# Driver4.net
KiCad netlist of a schematic drawn in Altium Designer
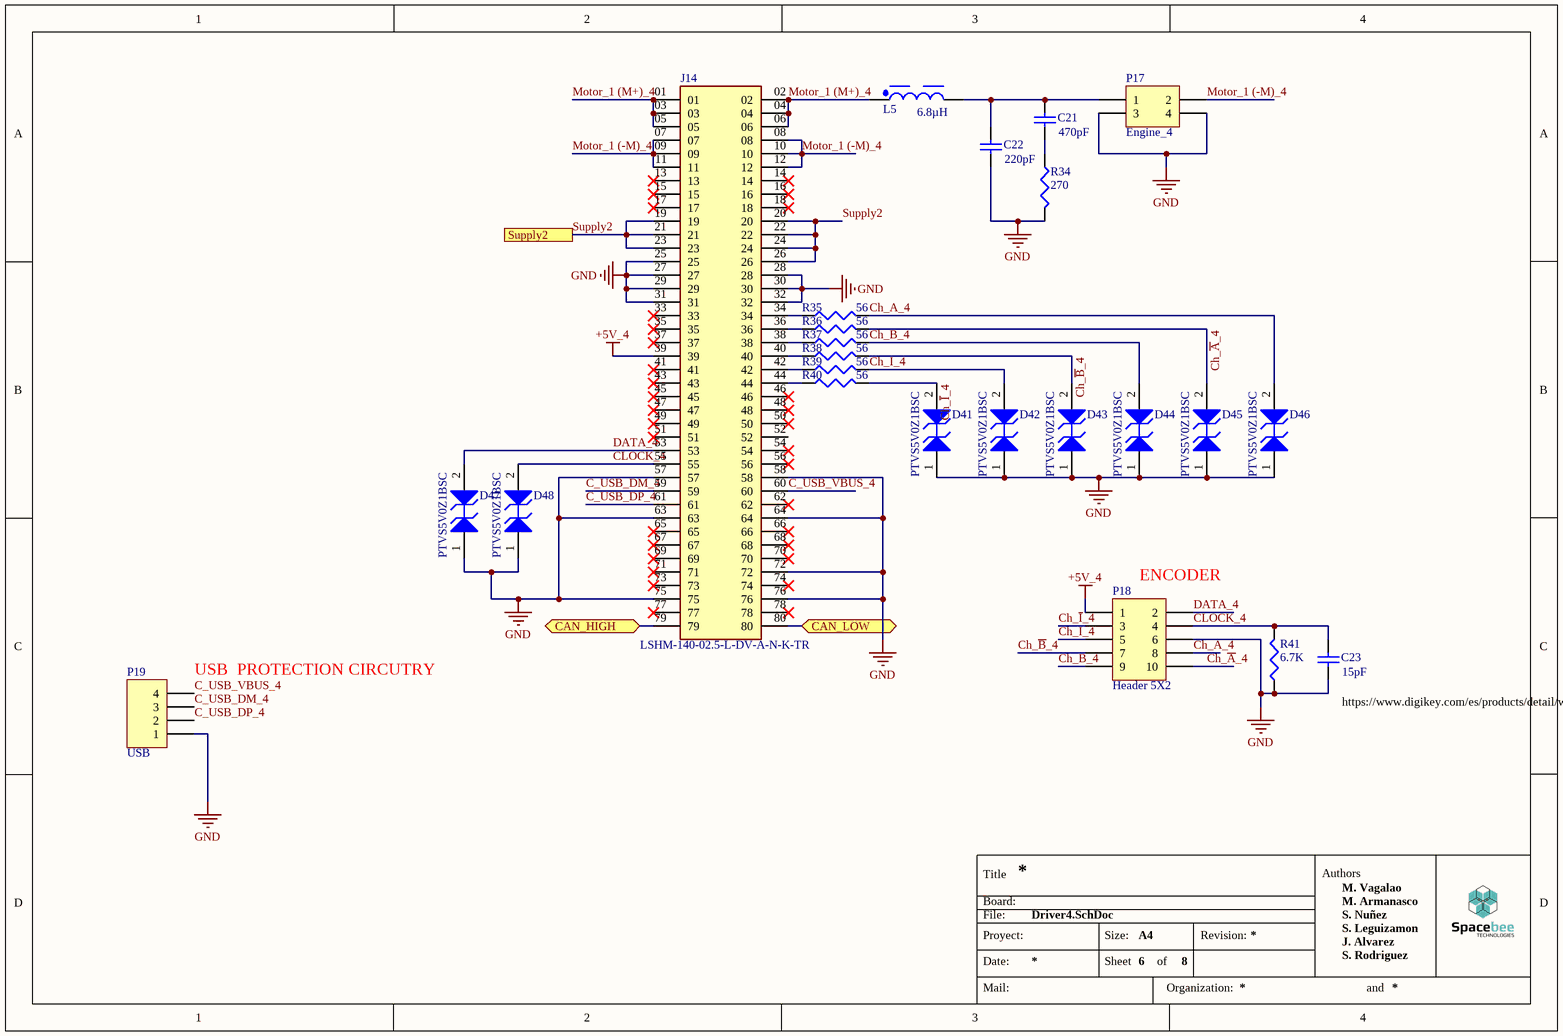
[diagram p0: Driver4.SchDoc]

(export (version "E")
  (design (tool "Eeschema 10.0.6"))
  (components
    (comp (ref "C21")
      (value "470pF")
      (footprint "1608[0603]")
      (description "Capacitor (Semiconductor SIM Model)")
      (fields (field (name "Comment") "Cap Semi") (field (name "PUBLISHER") "Altium Limited"))
      (libsource (lib "Miscellaneous Devices") (part "Cap Semi"))
    )
    (comp (ref "C22")
      (value "220pF")
      (footprint "1608[0603]")
      (description "Capacitor (Semiconductor SIM Model)")
      (fields (field (name "Comment") "Cap Semi") (field (name "PUBLISHER") "Altium Limited"))
      (libsource (lib "Miscellaneous Devices") (part "Cap Semi"))
    )
    (comp (ref "C23")
      (value "15pF")
      (footprint "1608[0603]")
      (description "Capacitor (Semiconductor SIM Model)")
      (fields (field (name "Comment") "Cap Semi") (field (name "PUBLISHER") "Altium Limited"))
      (libsource (lib "Miscellaneous Devices") (part "Cap Semi"))
    )
    (comp (ref "D41")
      (value "PTVS5V0Z1BSC")
      (footprint "SOD993B")
      (fields (field (name "MANUFACTURER") "On Semiconductor") (field (name "PARTNUMBER") "1SMB16CAT3"))
      (libsource (lib "DriverLib") (part "PTVS5V0Z1BSC"))
    )
    (comp (ref "D42")
      (value "PTVS5V0Z1BSC")
      (footprint "SOD993B")
      (fields (field (name "MANUFACTURER") "On Semiconductor") (field (name "PARTNUMBER") "1SMB16CAT3"))
      (libsource (lib "DriverLib") (part "PTVS5V0Z1BSC"))
    )
    (comp (ref "D43")
      (value "PTVS5V0Z1BSC")
      (footprint "SOD993B")
      (fields (field (name "MANUFACTURER") "On Semiconductor") (field (name "PARTNUMBER") "1SMB16CAT3"))
      (libsource (lib "DriverLib") (part "PTVS5V0Z1BSC"))
    )
    (comp (ref "D44")
      (value "PTVS5V0Z1BSC")
      (footprint "SOD993B")
      (fields (field (name "MANUFACTURER") "On Semiconductor") (field (name "PARTNUMBER") "1SMB16CAT3"))
      (libsource (lib "DriverLib") (part "PTVS5V0Z1BSC"))
    )
    (comp (ref "D45")
      (value "PTVS5V0Z1BSC")
      (footprint "SOD993B")
      (fields (field (name "MANUFACTURER") "On Semiconductor") (field (name "PARTNUMBER") "1SMB16CAT3"))
      (libsource (lib "DriverLib") (part "PTVS5V0Z1BSC"))
    )
    (comp (ref "D46")
      (value "PTVS5V0Z1BSC")
      (footprint "SOD993B")
      (fields (field (name "MANUFACTURER") "On Semiconductor") (field (name "PARTNUMBER") "1SMB16CAT3"))
      (libsource (lib "DriverLib") (part "PTVS5V0Z1BSC"))
    )
    (comp (ref "D47")
      (value "PTVS5V0Z1BSC")
      (footprint "SOD993B")
      (fields (field (name "MANUFACTURER") "On Semiconductor") (field (name "PARTNUMBER") "1SMB16CAT3"))
      (libsource (lib "DriverLib") (part "PTVS5V0Z1BSC"))
    )
    (comp (ref "D48")
      (value "PTVS5V0Z1BSC")
      (footprint "SOD993B")
      (fields (field (name "MANUFACTURER") "On Semiconductor") (field (name "PARTNUMBER") "1SMB16CAT3"))
      (libsource (lib "DriverLib") (part "PTVS5V0Z1BSC"))
    )
    (comp (ref "J14")
      (value "LSHM-140-02.5-L-DV-A-N-K-TR")
      (footprint "SAMTEC_LSHM-140-02.5-L-DV-A-N-K-TR")
      (description "LSHM - Samtec 0.50mm Razor Beam High-Speed Hermaphroditic Terminal / Socket Strip.")
      (libsource (lib "DriverLib") (part "LSHM-140-02.5-L-DV-A-N-K-TR"))
    )
    (comp (ref "L5")
      (value "6.8µH")
      (footprint "WE-XHMA_6060")
      (description "WE-XHMA SMD Power Inductor, size 1090, 6.8µH, 10.5A, 7.16mΩ")
      (fields
        (field (name "MANUFACTURER PART NUMBER") "78439369068")
        (field (name "MANUFACTURER") "Wurth Elektronik")
      )
      (libsource (lib "DriverLib") (part "78439369068"))
    )
    (comp (ref "P17")
      (value "Engine_4")
      (footprint "MOLEX_1724480004")
      (description "Header, 2-Pin, Dual row")
      (fields (field (name "PUBLISHER") "Altium Limited"))
      (libsource (lib "SpaceBee") (part "Header 2X2"))
    )
    (comp (ref "P18")
      (value "Header 5X2")
      (footprint "CONN_HIF3FC-14PA-2.54DS(71)_HIR")
      (description "Header, 5-Pin, Dual row")
      (fields (field (name "PUBLISHER") "Altium Limited"))
      (libsource (lib "DriverLib") (part "Header 5X2"))
    )
    (comp (ref "P19")
      (value "USB")
      (footprint "HDR1X4")
      (description "Header, 4-Pin")
      (fields (field (name "PUBLISHER") "Altium Limited"))
      (libsource (lib "Miscellaneous Connectors") (part "Header 4"))
    )
    (comp (ref "R34")
      (value "270")
      (footprint "J1-0603")
      (description "Resistor")
      (fields (field (name "Comment") "Res3") (field (name "PUBLISHER") "Altium Limited"))
      (libsource (lib "Miscellaneous Devices") (part "Res3"))
    )
    (comp (ref "R35")
      (value "56")
      (footprint "J1-0603")
      (description "Resistor")
      (fields (field (name "Comment") "Res3") (field (name "PUBLISHER") "Altium Limited"))
      (libsource (lib "Miscellaneous Devices") (part "Res3"))
    )
    (comp (ref "R36")
      (value "56")
      (footprint "J1-0603")
      (description "Resistor")
      (fields (field (name "Comment") "Res3") (field (name "PUBLISHER") "Altium Limited"))
      (libsource (lib "Miscellaneous Devices") (part "Res3"))
    )
    (comp (ref "R37")
      (value "56")
      (footprint "J1-0603")
      (description "Resistor")
      (fields (field (name "Comment") "Res3") (field (name "PUBLISHER") "Altium Limited"))
      (libsource (lib "Miscellaneous Devices") (part "Res3"))
    )
    (comp (ref "R38")
      (value "56")
      (footprint "J1-0603")
      (description "Resistor")
      (fields (field (name "Comment") "Res3") (field (name "PUBLISHER") "Altium Limited"))
      (libsource (lib "Miscellaneous Devices") (part "Res3"))
    )
    (comp (ref "R39")
      (value "56")
      (footprint "J1-0603")
      (description "Resistor")
      (fields (field (name "Comment") "Res3") (field (name "PUBLISHER") "Altium Limited"))
      (libsource (lib "Miscellaneous Devices") (part "Res3"))
    )
    (comp (ref "R40")
      (value "56")
      (footprint "J1-0603")
      (description "Resistor")
      (fields (field (name "Comment") "Res3") (field (name "PUBLISHER") "Altium Limited"))
      (libsource (lib "Miscellaneous Devices") (part "Res3"))
    )
    (comp (ref "R41")
      (value "6.7K")
      (footprint "J1-0603")
      (description "Resistor")
      (fields (field (name "Comment") "Res3") (field (name "PUBLISHER") "Altium Limited"))
      (libsource (lib "Miscellaneous Devices") (part "Res3"))
    )
  )
  (nets
    (net (code "1") (name "+5V_4") (class "Default")
      (node (ref "J14") (pin "39") (pinfunction "39_39") (pintype "passive"))
      (node (ref "P18") (pin "1") (pinfunction "1_1") (pintype "passive"))
    )
    (net (code "2") (name "/CAN_HIGH") (class "Default")
      (node (ref "J14") (pin "79") (pinfunction "79_79") (pintype "passive"))
    )
    (net (code "3") (name "/CAN_LOW") (class "Default")
      (node (ref "J14") (pin "80") (pinfunction "80_80") (pintype "passive"))
    )
    (net (code "4") (name "/CLOCK_4") (class "Default")
      (node (ref "C23") (pin "1") (pinfunction "1_1") (pintype "passive"))
      (node (ref "D48") (pin "2") (pinfunction "A2_2") (pintype "passive"))
      (node (ref "J14") (pin "55") (pinfunction "55_55") (pintype "passive"))
      (node (ref "P18") (pin "4") (pinfunction "4_4") (pintype "passive"))
      (node (ref "R41") (pin "2") (pinfunction "2_2") (pintype "passive"))
    )
    (net (code "5") (name "/C_USB_DM_4") (class "Default")
      (node (ref "J14") (pin "59") (pinfunction "59_59") (pintype "passive"))
      (node (ref "P19") (pin "3") (pinfunction "3_3") (pintype "passive"))
    )
    (net (code "6") (name "/C_USB_DP_4") (class "Default")
      (node (ref "J14") (pin "61") (pinfunction "61_61") (pintype "passive"))
      (node (ref "P19") (pin "2") (pinfunction "2_2") (pintype "passive"))
    )
    (net (code "7") (name "/C_USB_VBUS_4") (class "Default")
      (node (ref "J14") (pin "60") (pinfunction "60_60") (pintype "passive"))
      (node (ref "P19") (pin "4") (pinfunction "4_4") (pintype "passive"))
    )
    (net (code "8") (name "/Ch_A_4") (class "Default")
      (node (ref "D46") (pin "2") (pinfunction "A2_2") (pintype "passive"))
      (node (ref "P18") (pin "8") (pinfunction "8_8") (pintype "passive"))
      (node (ref "R35") (pin "2") (pinfunction "2_2") (pintype "passive"))
    )
    (net (code "9") (name "/Ch_B_4") (class "Default")
      (node (ref "D44") (pin "2") (pinfunction "A2_2") (pintype "passive"))
      (node (ref "P18") (pin "9") (pinfunction "9_9") (pintype "passive"))
      (node (ref "R37") (pin "2") (pinfunction "2_2") (pintype "passive"))
    )
    (net (code "10") (name "/Ch_I_4") (class "Default")
      (node (ref "D42") (pin "2") (pinfunction "A2_2") (pintype "passive"))
      (node (ref "P18") (pin "5") (pinfunction "5_5") (pintype "passive"))
      (node (ref "R39") (pin "2") (pinfunction "2_2") (pintype "passive"))
    )
    (net (code "11") (name "/Ch_~{A}_4") (class "Default")
      (node (ref "D45") (pin "2") (pinfunction "A2_2") (pintype "passive"))
      (node (ref "P18") (pin "10") (pinfunction "10_10") (pintype "passive"))
      (node (ref "R36") (pin "2") (pinfunction "2_2") (pintype "passive"))
    )
    (net (code "12") (name "/Ch_~{B}_4") (class "Default")
      (node (ref "D43") (pin "2") (pinfunction "A2_2") (pintype "passive"))
      (node (ref "P18") (pin "7") (pinfunction "7_7") (pintype "passive"))
      (node (ref "R38") (pin "2") (pinfunction "2_2") (pintype "passive"))
    )
    (net (code "13") (name "/Ch_~{I}_4") (class "Default")
      (node (ref "D41") (pin "2") (pinfunction "A2_2") (pintype "passive"))
      (node (ref "P18") (pin "3") (pinfunction "3_3") (pintype "passive"))
      (node (ref "R40") (pin "2") (pinfunction "2_2") (pintype "passive"))
    )
    (net (code "14") (name "/DATA_4") (class "Default")
      (node (ref "D47") (pin "2") (pinfunction "A2_2") (pintype "passive"))
      (node (ref "J14") (pin "53") (pinfunction "53_53") (pintype "passive"))
      (node (ref "P18") (pin "2") (pinfunction "2_2") (pintype "passive"))
    )
    (net (code "15") (name "/Motor_1 (-M)_4") (class "Default")
      (node (ref "J14") (pin "07") (pinfunction "07_07") (pintype "passive"))
      (node (ref "J14") (pin "08") (pinfunction "08_08") (pintype "passive"))
      (node (ref "J14") (pin "09") (pinfunction "09_09") (pintype "passive"))
      (node (ref "J14") (pin "10") (pinfunction "10_10") (pintype "passive"))
      (node (ref "J14") (pin "11") (pinfunction "11_11") (pintype "passive"))
      (node (ref "J14") (pin "12") (pinfunction "12_12") (pintype "passive"))
      (node (ref "P17") (pin "2") (pinfunction "2_2") (pintype "passive"))
    )
    (net (code "16") (name "/Motor_1 (M+)_4") (class "Default")
      (node (ref "J14") (pin "01") (pinfunction "01_01") (pintype "passive"))
      (node (ref "J14") (pin "02") (pinfunction "02_02") (pintype "passive"))
      (node (ref "J14") (pin "03") (pinfunction "03_03") (pintype "passive"))
      (node (ref "J14") (pin "04") (pinfunction "04_04") (pintype "passive"))
      (node (ref "J14") (pin "05") (pinfunction "05_05") (pintype "passive"))
      (node (ref "J14") (pin "06") (pinfunction "06_06") (pintype "passive"))
      (node (ref "L5") (pin "1") (pinfunction "1_1") (pintype "passive"))
    )
    (net (code "17") (name "/Supply2") (class "Default")
      (node (ref "J14") (pin "19") (pinfunction "19_19") (pintype "passive"))
      (node (ref "J14") (pin "20") (pinfunction "20_20") (pintype "passive"))
      (node (ref "J14") (pin "21") (pinfunction "21_21") (pintype "passive"))
      (node (ref "J14") (pin "22") (pinfunction "22_22") (pintype "passive"))
      (node (ref "J14") (pin "23") (pinfunction "23_23") (pintype "passive"))
      (node (ref "J14") (pin "24") (pinfunction "24_24") (pintype "passive"))
      (node (ref "J14") (pin "26") (pinfunction "26_26") (pintype "passive"))
    )
    (net (code "18") (name "GND") (class "Default")
      (node (ref "C22") (pin "2") (pinfunction "2_2") (pintype "passive"))
      (node (ref "C23") (pin "2") (pinfunction "2_2") (pintype "passive"))
      (node (ref "D41") (pin "1") (pinfunction "A1_1") (pintype "passive"))
      (node (ref "D42") (pin "1") (pinfunction "A1_1") (pintype "passive"))
      (node (ref "D43") (pin "1") (pinfunction "A1_1") (pintype "passive"))
      (node (ref "D44") (pin "1") (pinfunction "A1_1") (pintype "passive"))
      (node (ref "D45") (pin "1") (pinfunction "A1_1") (pintype "passive"))
      (node (ref "D46") (pin "1") (pinfunction "A1_1") (pintype "passive"))
      (node (ref "D47") (pin "1") (pinfunction "A1_1") (pintype "passive"))
      (node (ref "D48") (pin "1") (pinfunction "A1_1") (pintype "passive"))
      (node (ref "J14") (pin "25") (pinfunction "25_25") (pintype "passive"))
      (node (ref "J14") (pin "27") (pinfunction "27_27") (pintype "passive"))
      (node (ref "J14") (pin "28") (pinfunction "28_28") (pintype "passive"))
      (node (ref "J14") (pin "29") (pinfunction "29_29") (pintype "passive"))
      (node (ref "J14") (pin "30") (pinfunction "30_30") (pintype "passive"))
      (node (ref "J14") (pin "31") (pinfunction "31_31") (pintype "passive"))
      (node (ref "J14") (pin "32") (pinfunction "32_32") (pintype "passive"))
      (node (ref "J14") (pin "57") (pinfunction "57_57") (pintype "passive"))
      (node (ref "J14") (pin "58") (pinfunction "58_58") (pintype "passive"))
      (node (ref "J14") (pin "63") (pinfunction "63_63") (pintype "passive"))
      (node (ref "J14") (pin "64") (pinfunction "64_64") (pintype "passive"))
      (node (ref "J14") (pin "72") (pinfunction "72_72") (pintype "passive"))
      (node (ref "J14") (pin "75") (pinfunction "75_75") (pintype "passive"))
      (node (ref "J14") (pin "76") (pinfunction "76_76") (pintype "passive"))
      (node (ref "P17") (pin "3") (pinfunction "3_3") (pintype "passive"))
      (node (ref "P17") (pin "4") (pinfunction "4_4") (pintype "passive"))
      (node (ref "P18") (pin "6") (pinfunction "6_6") (pintype "passive"))
      (node (ref "P19") (pin "1") (pinfunction "1_1") (pintype "passive"))
      (node (ref "R34") (pin "2") (pinfunction "2_2") (pintype "passive"))
      (node (ref "R41") (pin "1") (pinfunction "1_1") (pintype "passive"))
    )
    (net (code "19") (name "Net-(C21-Pad1)") (class "Default")
      (node (ref "C21") (pin "1") (pinfunction "1_1") (pintype "passive"))
      (node (ref "C22") (pin "1") (pinfunction "1_1") (pintype "passive"))
      (node (ref "L5") (pin "2") (pinfunction "2_2") (pintype "passive"))
      (node (ref "P17") (pin "1") (pinfunction "1_1") (pintype "passive"))
    )
    (net (code "20") (name "Net-(C21-Pad2)") (class "Default")
      (node (ref "C21") (pin "2") (pinfunction "2_2") (pintype "passive"))
      (node (ref "R34") (pin "1") (pinfunction "1_1") (pintype "passive"))
    )
    (net (code "21") (name "Net-(J14-Pad34)") (class "Default")
      (node (ref "J14") (pin "34") (pinfunction "34_34") (pintype "passive"))
      (node (ref "R35") (pin "1") (pinfunction "1_1") (pintype "passive"))
    )
    (net (code "22") (name "Net-(J14-Pad36)") (class "Default")
      (node (ref "J14") (pin "36") (pinfunction "36_36") (pintype "passive"))
      (node (ref "R36") (pin "1") (pinfunction "1_1") (pintype "passive"))
    )
    (net (code "23") (name "Net-(J14-Pad38)") (class "Default")
      (node (ref "J14") (pin "38") (pinfunction "38_38") (pintype "passive"))
      (node (ref "R37") (pin "1") (pinfunction "1_1") (pintype "passive"))
    )
    (net (code "24") (name "Net-(J14-Pad40)") (class "Default")
      (node (ref "J14") (pin "40") (pinfunction "40_40") (pintype "passive"))
      (node (ref "R38") (pin "1") (pinfunction "1_1") (pintype "passive"))
    )
    (net (code "25") (name "Net-(J14-Pad42)") (class "Default")
      (node (ref "J14") (pin "42") (pinfunction "42_42") (pintype "passive"))
      (node (ref "R39") (pin "1") (pinfunction "1_1") (pintype "passive"))
    )
    (net (code "26") (name "Net-(J14-Pad44)") (class "Default")
      (node (ref "J14") (pin "44") (pinfunction "44_44") (pintype "passive"))
      (node (ref "R40") (pin "1") (pinfunction "1_1") (pintype "passive"))
    )
    (net (code "27") (name "unconnected-(J14-Pad13)") (class "Default")
      (node (ref "J14") (pin "13") (pinfunction "13_13") (pintype "passive+no_connect"))
    )
    (net (code "28") (name "unconnected-(J14-Pad14)") (class "Default")
      (node (ref "J14") (pin "14") (pinfunction "14_14") (pintype "passive+no_connect"))
    )
    (net (code "29") (name "unconnected-(J14-Pad15)") (class "Default")
      (node (ref "J14") (pin "15") (pinfunction "15_15") (pintype "passive+no_connect"))
    )
    (net (code "30") (name "unconnected-(J14-Pad16)") (class "Default")
      (node (ref "J14") (pin "16") (pinfunction "16_16") (pintype "passive+no_connect"))
    )
    (net (code "31") (name "unconnected-(J14-Pad17)") (class "Default")
      (node (ref "J14") (pin "17") (pinfunction "17_17") (pintype "passive+no_connect"))
    )
    (net (code "32") (name "unconnected-(J14-Pad18)") (class "Default")
      (node (ref "J14") (pin "18") (pinfunction "18_18") (pintype "passive+no_connect"))
    )
    (net (code "33") (name "unconnected-(J14-Pad33)") (class "Default")
      (node (ref "J14") (pin "33") (pinfunction "33_33") (pintype "passive+no_connect"))
    )
    (net (code "34") (name "unconnected-(J14-Pad35)") (class "Default")
      (node (ref "J14") (pin "35") (pinfunction "35_35") (pintype "passive+no_connect"))
    )
    (net (code "35") (name "unconnected-(J14-Pad37)") (class "Default")
      (node (ref "J14") (pin "37") (pinfunction "37_37") (pintype "passive+no_connect"))
    )
    (net (code "36") (name "unconnected-(J14-Pad41)") (class "Default")
      (node (ref "J14") (pin "41") (pinfunction "41_41") (pintype "passive+no_connect"))
    )
    (net (code "37") (name "unconnected-(J14-Pad43)") (class "Default")
      (node (ref "J14") (pin "43") (pinfunction "43_43") (pintype "passive+no_connect"))
    )
    (net (code "38") (name "unconnected-(J14-Pad45)") (class "Default")
      (node (ref "J14") (pin "45") (pinfunction "45_45") (pintype "passive+no_connect"))
    )
    (net (code "39") (name "unconnected-(J14-Pad46)") (class "Default")
      (node (ref "J14") (pin "46") (pinfunction "46_46") (pintype "passive+no_connect"))
    )
    (net (code "40") (name "unconnected-(J14-Pad47)") (class "Default")
      (node (ref "J14") (pin "47") (pinfunction "47_47") (pintype "passive+no_connect"))
    )
    (net (code "41") (name "unconnected-(J14-Pad48)") (class "Default")
      (node (ref "J14") (pin "48") (pinfunction "48_48") (pintype "passive+no_connect"))
    )
    (net (code "42") (name "unconnected-(J14-Pad49)") (class "Default")
      (node (ref "J14") (pin "49") (pinfunction "49_49") (pintype "passive+no_connect"))
    )
    (net (code "43") (name "unconnected-(J14-Pad50)") (class "Default")
      (node (ref "J14") (pin "50") (pinfunction "50_50") (pintype "passive+no_connect"))
    )
    (net (code "44") (name "unconnected-(J14-Pad51)") (class "Default")
      (node (ref "J14") (pin "51") (pinfunction "51_51") (pintype "passive+no_connect"))
    )
    (net (code "45") (name "unconnected-(J14-Pad52)") (class "Default")
      (node (ref "J14") (pin "52") (pinfunction "52_52") (pintype "passive"))
    )
    (net (code "46") (name "unconnected-(J14-Pad54)") (class "Default")
      (node (ref "J14") (pin "54") (pinfunction "54_54") (pintype "passive+no_connect"))
    )
    (net (code "47") (name "unconnected-(J14-Pad56)") (class "Default")
      (node (ref "J14") (pin "56") (pinfunction "56_56") (pintype "passive+no_connect"))
    )
    (net (code "48") (name "unconnected-(J14-Pad62)") (class "Default")
      (node (ref "J14") (pin "62") (pinfunction "62_62") (pintype "passive+no_connect"))
    )
    (net (code "49") (name "unconnected-(J14-Pad65)") (class "Default")
      (node (ref "J14") (pin "65") (pinfunction "65_65") (pintype "passive+no_connect"))
    )
    (net (code "50") (name "unconnected-(J14-Pad66)") (class "Default")
      (node (ref "J14") (pin "66") (pinfunction "66_66") (pintype "passive+no_connect"))
    )
    (net (code "51") (name "unconnected-(J14-Pad67)") (class "Default")
      (node (ref "J14") (pin "67") (pinfunction "67_67") (pintype "passive+no_connect"))
    )
    (net (code "52") (name "unconnected-(J14-Pad68)") (class "Default")
      (node (ref "J14") (pin "68") (pinfunction "68_68") (pintype "passive+no_connect"))
    )
    (net (code "53") (name "unconnected-(J14-Pad69)") (class "Default")
      (node (ref "J14") (pin "69") (pinfunction "69_69") (pintype "passive+no_connect"))
    )
    (net (code "54") (name "unconnected-(J14-Pad70)") (class "Default")
      (node (ref "J14") (pin "70") (pinfunction "70_70") (pintype "passive+no_connect"))
    )
    (net (code "55") (name "unconnected-(J14-Pad71)") (class "Default")
      (node (ref "J14") (pin "71") (pinfunction "71_71") (pintype "passive+no_connect"))
    )
    (net (code "56") (name "unconnected-(J14-Pad73)") (class "Default")
      (node (ref "J14") (pin "73") (pinfunction "73_73") (pintype "passive+no_connect"))
    )
    (net (code "57") (name "unconnected-(J14-Pad74)") (class "Default")
      (node (ref "J14") (pin "74") (pinfunction "74_74") (pintype "passive+no_connect"))
    )
    (net (code "58") (name "unconnected-(J14-Pad77)") (class "Default")
      (node (ref "J14") (pin "77") (pinfunction "77_77") (pintype "passive+no_connect"))
    )
    (net (code "59") (name "unconnected-(J14-Pad78)") (class "Default")
      (node (ref "J14") (pin "78") (pinfunction "78_78") (pintype "passive+no_connect"))
    )
  )
)
